# proximity.net
KiCad netlist of a schematic drawn in EAGLE
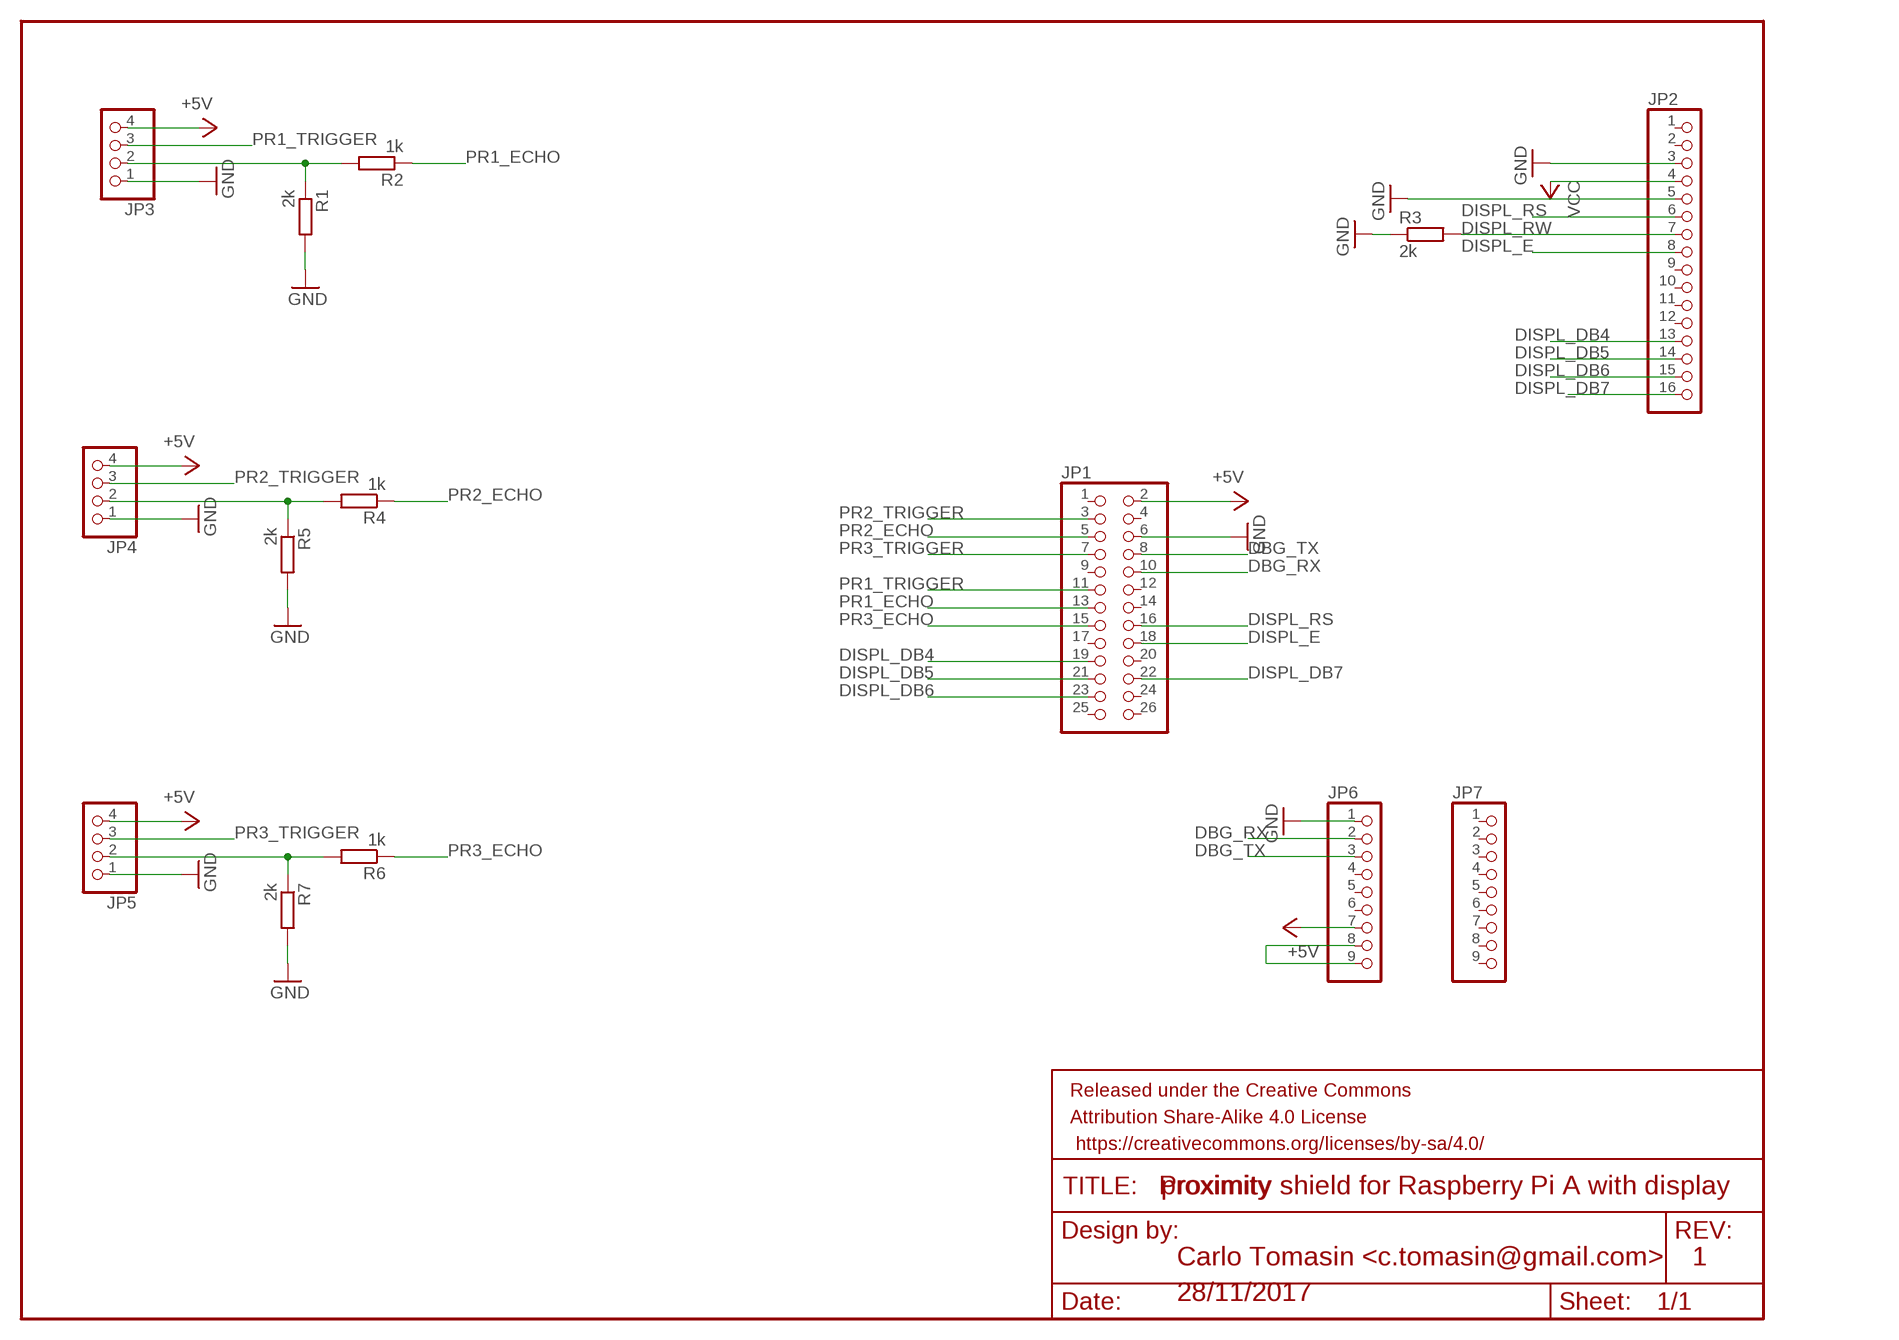
[diagram p0: schematic, sheet 1]

(export (version "E")
  (design (tool "Eeschema 10.0.6"))
  (components
    (comp (ref "FRAME1")
      (value "FRAME-LETTER")
      (footprint "eagle-import:CREATIVE_COMMONS")
      (libsource (lib "eagle-import") (part "FRAME-LETTER"))
    )
    (comp (ref "JP1")
      (value "PINHD-2X13")
      (footprint "eagle-import:2X13")
      (libsource (lib "eagle-import") (part "PINHD-2X13"))
    )
    (comp (ref "JP2")
      (value "PINHD-1X16")
      (footprint "eagle-import:1X16")
      (libsource (lib "eagle-import") (part "PINHD-1X16"))
    )
    (comp (ref "JP3")
      (value "PINHD-1X4")
      (footprint "eagle-import:1X04")
      (libsource (lib "eagle-import") (part "PINHD-1X4"))
    )
    (comp (ref "JP4")
      (value "PINHD-1X4")
      (footprint "eagle-import:1X04")
      (libsource (lib "eagle-import") (part "PINHD-1X4"))
    )
    (comp (ref "JP5")
      (value "PINHD-1X4")
      (footprint "eagle-import:1X04")
      (libsource (lib "eagle-import") (part "PINHD-1X4"))
    )
    (comp (ref "JP6")
      (value "PINHD-1X9")
      (footprint "eagle-import:1X09")
      (libsource (lib "eagle-import") (part "PINHD-1X9"))
    )
    (comp (ref "JP7")
      (value "PINHD-1X9")
      (footprint "eagle-import:1X09")
      (libsource (lib "eagle-import") (part "PINHD-1X9"))
    )
    (comp (ref "R1")
      (value "2k")
      (footprint "eagle-import:0204_7")
      (libsource (lib "eagle-import") (part "R-EU_0204/7"))
    )
    (comp (ref "R2")
      (value "1k")
      (footprint "eagle-import:0204_7")
      (libsource (lib "eagle-import") (part "R-EU_0204/7"))
    )
    (comp (ref "R3")
      (value "2k")
      (footprint "eagle-import:0204_7")
      (libsource (lib "eagle-import") (part "R-EU_0204/7"))
    )
    (comp (ref "R4")
      (value "1k")
      (footprint "eagle-import:0204_7")
      (libsource (lib "eagle-import") (part "R-EU_0204/7"))
    )
    (comp (ref "R5")
      (value "2k")
      (footprint "eagle-import:0204_7")
      (libsource (lib "eagle-import") (part "R-EU_0204/7"))
    )
    (comp (ref "R6")
      (value "1k")
      (footprint "eagle-import:0204_7")
      (libsource (lib "eagle-import") (part "R-EU_0204/7"))
    )
    (comp (ref "R7")
      (value "2k")
      (footprint "eagle-import:0204_7")
      (libsource (lib "eagle-import") (part "R-EU_0204/7"))
    )
  )
  (nets
    (net (code "1") (name "+5V") (class "Default")
      (node (ref "JP1") (pin "2") (pinfunction "2_2") (pintype "passive"))
      (node (ref "JP3") (pin "4") (pinfunction "4_4") (pintype "passive"))
      (node (ref "JP4") (pin "4") (pinfunction "4_4") (pintype "passive"))
      (node (ref "JP5") (pin "4") (pinfunction "4_4") (pintype "passive"))
      (node (ref "JP6") (pin "7") (pinfunction "7_7") (pintype "passive"))
    )
    (net (code "2") (name "/DBG_RX") (class "Default")
      (node (ref "JP1") (pin "10") (pinfunction "10_10") (pintype "passive"))
      (node (ref "JP6") (pin "2") (pinfunction "2_2") (pintype "passive"))
    )
    (net (code "3") (name "/DBG_TX") (class "Default")
      (node (ref "JP1") (pin "8") (pinfunction "8_8") (pintype "passive"))
      (node (ref "JP6") (pin "3") (pinfunction "3_3") (pintype "passive"))
    )
    (net (code "4") (name "/DISPL_DB4") (class "Default")
      (node (ref "JP1") (pin "19") (pinfunction "19_19") (pintype "passive"))
      (node (ref "JP2") (pin "13") (pinfunction "13_13") (pintype "passive"))
    )
    (net (code "5") (name "/DISPL_DB5") (class "Default")
      (node (ref "JP1") (pin "21") (pinfunction "21_21") (pintype "passive"))
      (node (ref "JP2") (pin "14") (pinfunction "14_14") (pintype "passive"))
    )
    (net (code "6") (name "/DISPL_DB6") (class "Default")
      (node (ref "JP1") (pin "23") (pinfunction "23_23") (pintype "passive"))
      (node (ref "JP2") (pin "15") (pinfunction "15_15") (pintype "passive"))
    )
    (net (code "7") (name "/DISPL_DB7") (class "Default")
      (node (ref "JP1") (pin "22") (pinfunction "22_22") (pintype "passive"))
      (node (ref "JP2") (pin "16") (pinfunction "16_16") (pintype "passive"))
    )
    (net (code "8") (name "/DISPL_E") (class "Default")
      (node (ref "JP1") (pin "18") (pinfunction "18_18") (pintype "passive"))
      (node (ref "JP2") (pin "8") (pinfunction "8_8") (pintype "passive"))
    )
    (net (code "9") (name "/DISPL_RS") (class "Default")
      (node (ref "JP1") (pin "16") (pinfunction "16_16") (pintype "passive"))
      (node (ref "JP2") (pin "6") (pinfunction "6_6") (pintype "passive"))
    )
    (net (code "10") (name "/DISPL_RW") (class "Default")
      (node (ref "JP2") (pin "7") (pinfunction "7_7") (pintype "passive"))
      (node (ref "R3") (pin "2") (pinfunction "2_2") (pintype "passive"))
    )
    (net (code "11") (name "/PR1_ECHO") (class "Default")
      (node (ref "JP1") (pin "13") (pinfunction "13_13") (pintype "passive"))
      (node (ref "R2") (pin "1") (pinfunction "1_1") (pintype "passive"))
    )
    (net (code "12") (name "/PR1_TRIGGER") (class "Default")
      (node (ref "JP1") (pin "11") (pinfunction "11_11") (pintype "passive"))
      (node (ref "JP3") (pin "3") (pinfunction "3_3") (pintype "passive"))
    )
    (net (code "13") (name "/PR2_ECHO") (class "Default")
      (node (ref "JP1") (pin "5") (pinfunction "5_5") (pintype "passive"))
      (node (ref "R4") (pin "1") (pinfunction "1_1") (pintype "passive"))
    )
    (net (code "14") (name "/PR2_TRIGGER") (class "Default")
      (node (ref "JP1") (pin "3") (pinfunction "3_3") (pintype "passive"))
      (node (ref "JP4") (pin "3") (pinfunction "3_3") (pintype "passive"))
    )
    (net (code "15") (name "/PR3_ECHO") (class "Default")
      (node (ref "JP1") (pin "15") (pinfunction "15_15") (pintype "passive"))
      (node (ref "R6") (pin "1") (pinfunction "1_1") (pintype "passive"))
    )
    (net (code "16") (name "/PR3_TRIGGER") (class "Default")
      (node (ref "JP1") (pin "7") (pinfunction "7_7") (pintype "passive"))
      (node (ref "JP5") (pin "3") (pinfunction "3_3") (pintype "passive"))
    )
    (net (code "17") (name "GND") (class "Default")
      (node (ref "JP1") (pin "6") (pinfunction "6_6") (pintype "passive"))
      (node (ref "JP2") (pin "3") (pinfunction "3_3") (pintype "passive"))
      (node (ref "JP2") (pin "5") (pinfunction "5_5") (pintype "passive"))
      (node (ref "JP3") (pin "1") (pinfunction "1_1") (pintype "passive"))
      (node (ref "JP4") (pin "1") (pinfunction "1_1") (pintype "passive"))
      (node (ref "JP5") (pin "1") (pinfunction "1_1") (pintype "passive"))
      (node (ref "JP6") (pin "1") (pinfunction "1_1") (pintype "passive"))
      (node (ref "R1") (pin "2") (pinfunction "2_2") (pintype "passive"))
      (node (ref "R3") (pin "1") (pinfunction "1_1") (pintype "passive"))
      (node (ref "R5") (pin "2") (pinfunction "2_2") (pintype "passive"))
      (node (ref "R7") (pin "2") (pinfunction "2_2") (pintype "passive"))
    )
    (net (code "18") (name "Net-(JP3-Pad2)") (class "Default")
      (node (ref "JP3") (pin "2") (pinfunction "2_2") (pintype "passive"))
      (node (ref "R1") (pin "1") (pinfunction "1_1") (pintype "passive"))
      (node (ref "R2") (pin "2") (pinfunction "2_2") (pintype "passive"))
    )
    (net (code "19") (name "Net-(JP4-Pad2)") (class "Default")
      (node (ref "JP4") (pin "2") (pinfunction "2_2") (pintype "passive"))
      (node (ref "R4") (pin "2") (pinfunction "2_2") (pintype "passive"))
      (node (ref "R5") (pin "1") (pinfunction "1_1") (pintype "passive"))
    )
    (net (code "20") (name "Net-(JP5-Pad2)") (class "Default")
      (node (ref "JP5") (pin "2") (pinfunction "2_2") (pintype "passive"))
      (node (ref "R6") (pin "2") (pinfunction "2_2") (pintype "passive"))
      (node (ref "R7") (pin "1") (pinfunction "1_1") (pintype "passive"))
    )
    (net (code "21") (name "Net-(JP6-Pad8)") (class "Default")
      (node (ref "JP6") (pin "8") (pinfunction "8_8") (pintype "passive"))
      (node (ref "JP6") (pin "9") (pinfunction "9_9") (pintype "passive"))
    )
    (net (code "22") (name "VCC") (class "Default")
      (node (ref "JP2") (pin "4") (pinfunction "4_4") (pintype "passive"))
    )
    (net (code "23") (name "unconnected-(JP1-Pad1)") (class "Default")
      (node (ref "JP1") (pin "1") (pinfunction "1_1") (pintype "passive"))
    )
    (net (code "24") (name "unconnected-(JP1-Pad4)") (class "Default")
      (node (ref "JP1") (pin "4") (pinfunction "4_4") (pintype "passive"))
    )
    (net (code "25") (name "unconnected-(JP1-Pad9)") (class "Default")
      (node (ref "JP1") (pin "9") (pinfunction "9_9") (pintype "passive"))
    )
    (net (code "26") (name "unconnected-(JP1-Pad12)") (class "Default")
      (node (ref "JP1") (pin "12") (pinfunction "12_12") (pintype "passive"))
    )
    (net (code "27") (name "unconnected-(JP1-Pad14)") (class "Default")
      (node (ref "JP1") (pin "14") (pinfunction "14_14") (pintype "passive"))
    )
    (net (code "28") (name "unconnected-(JP1-Pad17)") (class "Default")
      (node (ref "JP1") (pin "17") (pinfunction "17_17") (pintype "passive"))
    )
    (net (code "29") (name "unconnected-(JP1-Pad20)") (class "Default")
      (node (ref "JP1") (pin "20") (pinfunction "20_20") (pintype "passive"))
    )
    (net (code "30") (name "unconnected-(JP1-Pad24)") (class "Default")
      (node (ref "JP1") (pin "24") (pinfunction "24_24") (pintype "passive"))
    )
    (net (code "31") (name "unconnected-(JP1-Pad25)") (class "Default")
      (node (ref "JP1") (pin "25") (pinfunction "25_25") (pintype "passive"))
    )
    (net (code "32") (name "unconnected-(JP1-Pad26)") (class "Default")
      (node (ref "JP1") (pin "26") (pinfunction "26_26") (pintype "passive"))
    )
    (net (code "33") (name "unconnected-(JP2-Pad1)") (class "Default")
      (node (ref "JP2") (pin "1") (pinfunction "1_1") (pintype "passive"))
    )
    (net (code "34") (name "unconnected-(JP2-Pad2)") (class "Default")
      (node (ref "JP2") (pin "2") (pinfunction "2_2") (pintype "passive"))
    )
    (net (code "35") (name "unconnected-(JP2-Pad9)") (class "Default")
      (node (ref "JP2") (pin "9") (pinfunction "9_9") (pintype "passive"))
    )
    (net (code "36") (name "unconnected-(JP2-Pad10)") (class "Default")
      (node (ref "JP2") (pin "10") (pinfunction "10_10") (pintype "passive"))
    )
    (net (code "37") (name "unconnected-(JP2-Pad11)") (class "Default")
      (node (ref "JP2") (pin "11") (pinfunction "11_11") (pintype "passive"))
    )
    (net (code "38") (name "unconnected-(JP2-Pad12)") (class "Default")
      (node (ref "JP2") (pin "12") (pinfunction "12_12") (pintype "passive"))
    )
    (net (code "39") (name "unconnected-(JP6-Pad4)") (class "Default")
      (node (ref "JP6") (pin "4") (pinfunction "4_4") (pintype "passive"))
    )
    (net (code "40") (name "unconnected-(JP6-Pad5)") (class "Default")
      (node (ref "JP6") (pin "5") (pinfunction "5_5") (pintype "passive"))
    )
    (net (code "41") (name "unconnected-(JP6-Pad6)") (class "Default")
      (node (ref "JP6") (pin "6") (pinfunction "6_6") (pintype "passive"))
    )
    (net (code "42") (name "unconnected-(JP7-Pad1)") (class "Default")
      (node (ref "JP7") (pin "1") (pinfunction "1_1") (pintype "passive"))
    )
    (net (code "43") (name "unconnected-(JP7-Pad2)") (class "Default")
      (node (ref "JP7") (pin "2") (pinfunction "2_2") (pintype "passive"))
    )
    (net (code "44") (name "unconnected-(JP7-Pad3)") (class "Default")
      (node (ref "JP7") (pin "3") (pinfunction "3_3") (pintype "passive"))
    )
    (net (code "45") (name "unconnected-(JP7-Pad4)") (class "Default")
      (node (ref "JP7") (pin "4") (pinfunction "4_4") (pintype "passive"))
    )
    (net (code "46") (name "unconnected-(JP7-Pad5)") (class "Default")
      (node (ref "JP7") (pin "5") (pinfunction "5_5") (pintype "passive"))
    )
    (net (code "47") (name "unconnected-(JP7-Pad6)") (class "Default")
      (node (ref "JP7") (pin "6") (pinfunction "6_6") (pintype "passive"))
    )
    (net (code "48") (name "unconnected-(JP7-Pad7)") (class "Default")
      (node (ref "JP7") (pin "7") (pinfunction "7_7") (pintype "passive"))
    )
    (net (code "49") (name "unconnected-(JP7-Pad8)") (class "Default")
      (node (ref "JP7") (pin "8") (pinfunction "8_8") (pintype "passive"))
    )
    (net (code "50") (name "unconnected-(JP7-Pad9)") (class "Default")
      (node (ref "JP7") (pin "9") (pinfunction "9_9") (pintype "passive"))
    )
  )
)
